# Power.net
KiCad netlist of a schematic drawn in Altium Designer
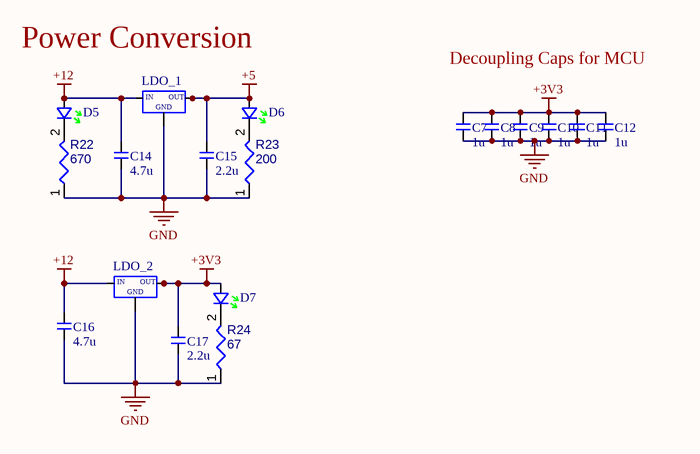
[diagram p0: Power.SchDoc]

(export (version "E")
  (design (tool "Eeschema 10.0.6"))
  (components
    (comp (ref "C7")
      (value "1u")
      (footprint "CAP-0603")
      (fields (field (name "SOURCE") "ife19_Elec_Library.SchLib"))
      (libsource (lib "Illini Formula Electric") (part "CAP-0603"))
    )
    (comp (ref "C8")
      (value "1u")
      (footprint "CAP-0603")
      (fields (field (name "SOURCE") "ife19_Elec_Library.SchLib"))
      (libsource (lib "Illini Formula Electric") (part "CAP-0603"))
    )
    (comp (ref "C9")
      (value "1u")
      (footprint "CAP-0603")
      (fields (field (name "SOURCE") "ife19_Elec_Library.SchLib"))
      (libsource (lib "Illini Formula Electric") (part "CAP-0603"))
    )
    (comp (ref "C10")
      (value "1u")
      (footprint "CAP-0603")
      (fields (field (name "SOURCE") "ife19_Elec_Library.SchLib"))
      (libsource (lib "Illini Formula Electric") (part "CAP-0603"))
    )
    (comp (ref "C11")
      (value "1u")
      (footprint "CAP-0603")
      (fields (field (name "SOURCE") "ife19_Elec_Library.SchLib"))
      (libsource (lib "Illini Formula Electric") (part "CAP-0603"))
    )
    (comp (ref "C12")
      (value "1u")
      (footprint "CAP-0603")
      (fields (field (name "SOURCE") "ife19_Elec_Library.SchLib"))
      (libsource (lib "Illini Formula Electric") (part "CAP-0603"))
    )
    (comp (ref "C14")
      (value "4.7u")
      (footprint "CAP-0603")
      (fields (field (name "SOURCE") "ife19_Elec_Library.SchLib"))
      (libsource (lib "Illini Formula Electric") (part "CAP-0603"))
    )
    (comp (ref "C15")
      (value "2.2u")
      (footprint "CAP-0603")
      (fields (field (name "SOURCE") "ife19_Elec_Library.SchLib"))
      (libsource (lib "Illini Formula Electric") (part "CAP-0603"))
    )
    (comp (ref "C16")
      (value "4.7u")
      (footprint "CAP-0603")
      (fields (field (name "SOURCE") "ife19_Elec_Library.SchLib"))
      (libsource (lib "Illini Formula Electric") (part "CAP-0603"))
    )
    (comp (ref "C17")
      (value "2.2u")
      (footprint "CAP-0603")
      (fields (field (name "SOURCE") "ife19_Elec_Library.SchLib"))
      (libsource (lib "Illini Formula Electric") (part "CAP-0603"))
    )
    (comp (ref "D5")
      (value "LEDGREEN-1806-RIGHT")
      (footprint "LEDGREEN-1806-RIGHT")
      (fields (field (name "SOURCE") "ife19_Elec_Library.SchLib"))
      (libsource (lib "Illini Formula Electric") (part "LEDGREEN-1806-RIGHT"))
    )
    (comp (ref "D6")
      (value "LEDGREEN-1806-RIGHT")
      (footprint "LEDGREEN-1806-RIGHT")
      (fields (field (name "SOURCE") "ife19_Elec_Library.SchLib"))
      (libsource (lib "Illini Formula Electric") (part "LEDGREEN-1806-RIGHT"))
    )
    (comp (ref "D7")
      (value "LEDGREEN-1806-RIGHT")
      (footprint "LEDGREEN-1806-RIGHT")
      (fields (field (name "SOURCE") "ife19_Elec_Library.SchLib"))
      (libsource (lib "Illini Formula Electric") (part "LEDGREEN-1806-RIGHT"))
    )
    (comp (ref "LDO_1")
      (value "LDO-SOT223_SPX1117")
      (footprint "SOT223")
      (fields (field (name "SOURCE") "ife19_Elec_Library.SchLib"))
      (libsource (lib "Illini Formula Electric") (part "LDO-SOT223_SPX1117"))
    )
    (comp (ref "LDO_2")
      (value "LDO-SOT223_SPX1117")
      (footprint "SOT223")
      (fields (field (name "SOURCE") "ife19_Elec_Library.SchLib"))
      (libsource (lib "Illini Formula Electric") (part "LDO-SOT223_SPX1117"))
    )
    (comp (ref "R22")
      (value "670")
      (footprint "RESC0805(2012)_L")
      (description "Chip Resistor, 43,2 kOhms, +/-1 %, 63 mW, -55 to 155 degC, 0402")
      (fields (field (name "AVAILABLE PREVIEW IMAGES") "2D"))
      (libsource (lib "Illini Formula Electric") (part "Symbol"))
    )
    (comp (ref "R23")
      (value "200")
      (footprint "RESC0805(2012)_L")
      (description "Chip Resistor, 43,2 kOhms, +/-1 %, 63 mW, -55 to 155 degC, 0402")
      (fields (field (name "AVAILABLE PREVIEW IMAGES") "2D"))
      (libsource (lib "Illini Formula Electric") (part "Symbol"))
    )
    (comp (ref "R24")
      (value "67")
      (footprint "RESC0805(2012)_L")
      (description "Chip Resistor, 43,2 kOhms, +/-1 %, 63 mW, -55 to 155 degC, 0402")
      (fields (field (name "AVAILABLE PREVIEW IMAGES") "2D"))
      (libsource (lib "Illini Formula Electric") (part "Symbol"))
    )
  )
  (nets
    (net (code "1") (name "+3V3") (class "Default")
      (node (ref "C10") (pin "1") (pinfunction "1_1") (pintype "passive"))
      (node (ref "C11") (pin "1") (pinfunction "1_1") (pintype "passive"))
      (node (ref "C12") (pin "1") (pinfunction "1_1") (pintype "passive"))
      (node (ref "C17") (pin "1") (pinfunction "1_1") (pintype "passive"))
      (node (ref "C7") (pin "1") (pinfunction "1_1") (pintype "passive"))
      (node (ref "C8") (pin "1") (pinfunction "1_1") (pintype "passive"))
      (node (ref "C9") (pin "1") (pinfunction "1_1") (pintype "passive"))
      (node (ref "D7") (pin "A") (pinfunction "A_A") (pintype "passive"))
      (node (ref "LDO_2") (pin "2") (pinfunction "2_2") (pintype "passive"))
      (node (ref "LDO_2") (pin "4") (pinfunction "4_4") (pintype "passive"))
    )
    (net (code "2") (name "+5") (class "Default")
      (node (ref "C15") (pin "1") (pinfunction "1_1") (pintype "passive"))
      (node (ref "D6") (pin "A") (pinfunction "A_A") (pintype "passive"))
      (node (ref "LDO_1") (pin "2") (pinfunction "2_2") (pintype "passive"))
      (node (ref "LDO_1") (pin "4") (pinfunction "4_4") (pintype "passive"))
    )
    (net (code "3") (name "+12") (class "Default")
      (node (ref "C14") (pin "1") (pinfunction "1_1") (pintype "passive"))
      (node (ref "C16") (pin "1") (pinfunction "1_1") (pintype "passive"))
      (node (ref "D5") (pin "A") (pinfunction "A_A") (pintype "passive"))
      (node (ref "LDO_1") (pin "3") (pinfunction "3_3") (pintype "passive"))
      (node (ref "LDO_2") (pin "3") (pinfunction "3_3") (pintype "passive"))
    )
    (net (code "4") (name "GND") (class "Default")
      (node (ref "C10") (pin "2") (pinfunction "2_2") (pintype "passive"))
      (node (ref "C11") (pin "2") (pinfunction "2_2") (pintype "passive"))
      (node (ref "C12") (pin "2") (pinfunction "2_2") (pintype "passive"))
      (node (ref "C14") (pin "2") (pinfunction "2_2") (pintype "passive"))
      (node (ref "C15") (pin "2") (pinfunction "2_2") (pintype "passive"))
      (node (ref "C16") (pin "2") (pinfunction "2_2") (pintype "passive"))
      (node (ref "C17") (pin "2") (pinfunction "2_2") (pintype "passive"))
      (node (ref "C7") (pin "2") (pinfunction "2_2") (pintype "passive"))
      (node (ref "C8") (pin "2") (pinfunction "2_2") (pintype "passive"))
      (node (ref "C9") (pin "2") (pinfunction "2_2") (pintype "passive"))
      (node (ref "LDO_1") (pin "1") (pinfunction "1_1") (pintype "passive"))
      (node (ref "LDO_2") (pin "1") (pinfunction "1_1") (pintype "passive"))
      (node (ref "R22") (pin "1") (pinfunction "1_1") (pintype "passive"))
      (node (ref "R23") (pin "1") (pinfunction "1_1") (pintype "passive"))
      (node (ref "R24") (pin "1") (pinfunction "1_1") (pintype "passive"))
    )
    (net (code "5") (name "Net-(D5-PadK)") (class "Default")
      (node (ref "D5") (pin "K") (pinfunction "K_K") (pintype "passive"))
      (node (ref "R22") (pin "2") (pinfunction "2_2") (pintype "passive"))
    )
    (net (code "6") (name "Net-(D6-PadK)") (class "Default")
      (node (ref "D6") (pin "K") (pinfunction "K_K") (pintype "passive"))
      (node (ref "R23") (pin "2") (pinfunction "2_2") (pintype "passive"))
    )
    (net (code "7") (name "Net-(D7-PadK)") (class "Default")
      (node (ref "D7") (pin "K") (pinfunction "K_K") (pintype "passive"))
      (node (ref "R24") (pin "2") (pinfunction "2_2") (pintype "passive"))
    )
  )
)
